# board2.net
KiCad netlist of a schematic drawn in EAGLE
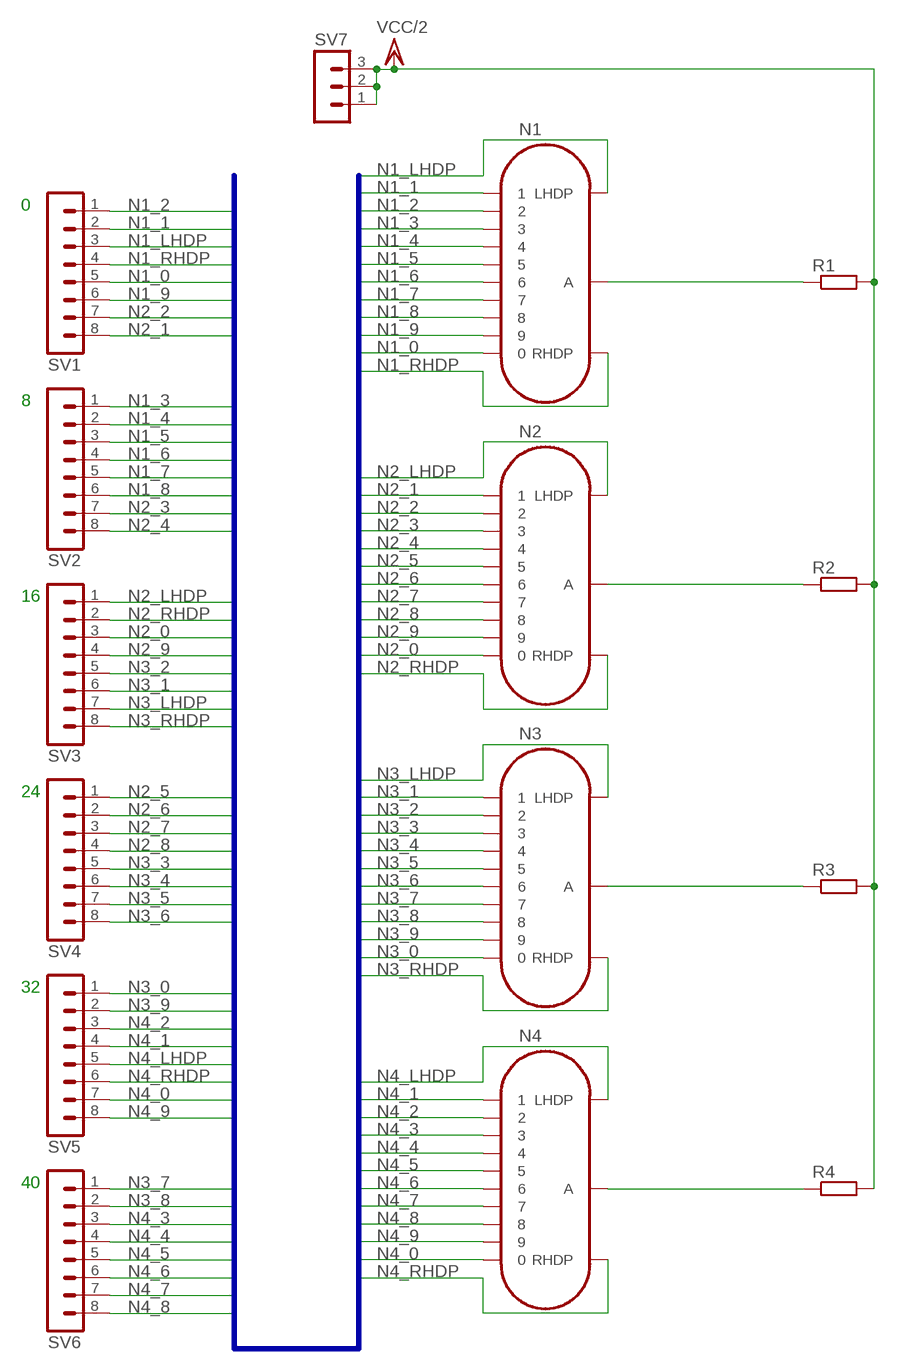
[diagram p0: schematic, sheet 1]

(export (version "E")
  (design (tool "Eeschema 10.0.6"))
  (components
    (comp (ref "N1")
      (value "IN-14")
      (footprint "eagle-import:IN-14")
      (libsource (lib "eagle-import") (part "IN-14"))
    )
    (comp (ref "N2")
      (value "IN-14")
      (footprint "eagle-import:IN-14")
      (libsource (lib "eagle-import") (part "IN-14"))
    )
    (comp (ref "N3")
      (value "IN-14")
      (footprint "eagle-import:IN-14")
      (libsource (lib "eagle-import") (part "IN-14"))
    )
    (comp (ref "N4")
      (value "IN-14")
      (footprint "eagle-import:IN-14")
      (libsource (lib "eagle-import") (part "IN-14"))
    )
    (comp (ref "R1")
      (value "R-EU_0207/7")
      (footprint "eagle-import:0207_7")
      (libsource (lib "eagle-import") (part "R-EU_0207/7"))
    )
    (comp (ref "R2")
      (value "R-EU_0207/7")
      (footprint "eagle-import:0207_7")
      (libsource (lib "eagle-import") (part "R-EU_0207/7"))
    )
    (comp (ref "R3")
      (value "R-EU_0207/7")
      (footprint "eagle-import:0207_7")
      (libsource (lib "eagle-import") (part "R-EU_0207/7"))
    )
    (comp (ref "R4")
      (value "R-EU_0207/7")
      (footprint "eagle-import:0207_7")
      (libsource (lib "eagle-import") (part "R-EU_0207/7"))
    )
    (comp (ref "SV1")
      (value "MA08-1")
      (footprint "eagle-import:MA08-1")
      (libsource (lib "eagle-import") (part "MA08-1"))
    )
    (comp (ref "SV2")
      (value "MA08-1")
      (footprint "eagle-import:MA08-1")
      (libsource (lib "eagle-import") (part "MA08-1"))
    )
    (comp (ref "SV3")
      (value "MA08-1")
      (footprint "eagle-import:MA08-1")
      (libsource (lib "eagle-import") (part "MA08-1"))
    )
    (comp (ref "SV4")
      (value "MA08-1")
      (footprint "eagle-import:MA08-1")
      (libsource (lib "eagle-import") (part "MA08-1"))
    )
    (comp (ref "SV5")
      (value "MA08-1")
      (footprint "eagle-import:MA08-1")
      (libsource (lib "eagle-import") (part "MA08-1"))
    )
    (comp (ref "SV6")
      (value "MA08-1")
      (footprint "eagle-import:MA08-1")
      (libsource (lib "eagle-import") (part "MA08-1"))
    )
    (comp (ref "SV7")
      (value "MA03-1")
      (footprint "eagle-import:MA03-1")
      (libsource (lib "eagle-import") (part "MA03-1"))
    )
  )
  (nets
    (net (code "1") (name "/N1_0") (class "Default")
      (node (ref "N1") (pin "0") (pinfunction "0_0") (pintype "bidirectional"))
      (node (ref "SV1") (pin "5") (pinfunction "5_5") (pintype "passive"))
    )
    (net (code "2") (name "/N1_1") (class "Default")
      (node (ref "N1") (pin "1") (pinfunction "1_1") (pintype "bidirectional"))
      (node (ref "SV1") (pin "2") (pinfunction "2_2") (pintype "passive"))
    )
    (net (code "3") (name "/N1_2") (class "Default")
      (node (ref "N1") (pin "2") (pinfunction "2_2") (pintype "bidirectional"))
      (node (ref "SV1") (pin "1") (pinfunction "1_1") (pintype "passive"))
    )
    (net (code "4") (name "/N1_3") (class "Default")
      (node (ref "N1") (pin "3") (pinfunction "3_3") (pintype "bidirectional"))
      (node (ref "SV2") (pin "1") (pinfunction "1_1") (pintype "passive"))
    )
    (net (code "5") (name "/N1_4") (class "Default")
      (node (ref "N1") (pin "4") (pinfunction "4_4") (pintype "bidirectional"))
      (node (ref "SV2") (pin "2") (pinfunction "2_2") (pintype "passive"))
    )
    (net (code "6") (name "/N1_5") (class "Default")
      (node (ref "N1") (pin "5") (pinfunction "5_5") (pintype "bidirectional"))
      (node (ref "SV2") (pin "3") (pinfunction "3_3") (pintype "passive"))
    )
    (net (code "7") (name "/N1_6") (class "Default")
      (node (ref "N1") (pin "6") (pinfunction "6_6") (pintype "bidirectional"))
      (node (ref "SV2") (pin "4") (pinfunction "4_4") (pintype "passive"))
    )
    (net (code "8") (name "/N1_7") (class "Default")
      (node (ref "N1") (pin "7") (pinfunction "7_7") (pintype "bidirectional"))
      (node (ref "SV2") (pin "5") (pinfunction "5_5") (pintype "passive"))
    )
    (net (code "9") (name "/N1_8") (class "Default")
      (node (ref "N1") (pin "8") (pinfunction "8_8") (pintype "bidirectional"))
      (node (ref "SV2") (pin "6") (pinfunction "6_6") (pintype "passive"))
    )
    (net (code "10") (name "/N1_9") (class "Default")
      (node (ref "N1") (pin "9") (pinfunction "9_9") (pintype "bidirectional"))
      (node (ref "SV1") (pin "6") (pinfunction "6_6") (pintype "passive"))
    )
    (net (code "11") (name "/N1_LHDP") (class "Default")
      (node (ref "N1") (pin "LHDP") (pinfunction "LHDP_LHDP") (pintype "bidirectional"))
      (node (ref "SV1") (pin "3") (pinfunction "3_3") (pintype "passive"))
    )
    (net (code "12") (name "/N1_RHDP") (class "Default")
      (node (ref "N1") (pin "RHDP") (pinfunction "RHDP_RHDP") (pintype "bidirectional"))
      (node (ref "SV1") (pin "4") (pinfunction "4_4") (pintype "passive"))
    )
    (net (code "13") (name "/N2_0") (class "Default")
      (node (ref "N2") (pin "0") (pinfunction "0_0") (pintype "bidirectional"))
      (node (ref "SV3") (pin "3") (pinfunction "3_3") (pintype "passive"))
    )
    (net (code "14") (name "/N2_1") (class "Default")
      (node (ref "N2") (pin "1") (pinfunction "1_1") (pintype "bidirectional"))
      (node (ref "SV1") (pin "8") (pinfunction "8_8") (pintype "passive"))
    )
    (net (code "15") (name "/N2_2") (class "Default")
      (node (ref "N2") (pin "2") (pinfunction "2_2") (pintype "bidirectional"))
      (node (ref "SV1") (pin "7") (pinfunction "7_7") (pintype "passive"))
    )
    (net (code "16") (name "/N2_3") (class "Default")
      (node (ref "N2") (pin "3") (pinfunction "3_3") (pintype "bidirectional"))
      (node (ref "SV2") (pin "7") (pinfunction "7_7") (pintype "passive"))
    )
    (net (code "17") (name "/N2_4") (class "Default")
      (node (ref "N2") (pin "4") (pinfunction "4_4") (pintype "bidirectional"))
      (node (ref "SV2") (pin "8") (pinfunction "8_8") (pintype "passive"))
    )
    (net (code "18") (name "/N2_5") (class "Default")
      (node (ref "N2") (pin "5") (pinfunction "5_5") (pintype "bidirectional"))
      (node (ref "SV4") (pin "1") (pinfunction "1_1") (pintype "passive"))
    )
    (net (code "19") (name "/N2_6") (class "Default")
      (node (ref "N2") (pin "6") (pinfunction "6_6") (pintype "bidirectional"))
      (node (ref "SV4") (pin "2") (pinfunction "2_2") (pintype "passive"))
    )
    (net (code "20") (name "/N2_7") (class "Default")
      (node (ref "N2") (pin "7") (pinfunction "7_7") (pintype "bidirectional"))
      (node (ref "SV4") (pin "3") (pinfunction "3_3") (pintype "passive"))
    )
    (net (code "21") (name "/N2_8") (class "Default")
      (node (ref "N2") (pin "8") (pinfunction "8_8") (pintype "bidirectional"))
      (node (ref "SV4") (pin "4") (pinfunction "4_4") (pintype "passive"))
    )
    (net (code "22") (name "/N2_9") (class "Default")
      (node (ref "N2") (pin "9") (pinfunction "9_9") (pintype "bidirectional"))
      (node (ref "SV3") (pin "4") (pinfunction "4_4") (pintype "passive"))
    )
    (net (code "23") (name "/N2_LHDP") (class "Default")
      (node (ref "N2") (pin "LHDP") (pinfunction "LHDP_LHDP") (pintype "bidirectional"))
      (node (ref "SV3") (pin "1") (pinfunction "1_1") (pintype "passive"))
    )
    (net (code "24") (name "/N2_RHDP") (class "Default")
      (node (ref "N2") (pin "RHDP") (pinfunction "RHDP_RHDP") (pintype "bidirectional"))
      (node (ref "SV3") (pin "2") (pinfunction "2_2") (pintype "passive"))
    )
    (net (code "25") (name "/N3_0") (class "Default")
      (node (ref "N3") (pin "0") (pinfunction "0_0") (pintype "bidirectional"))
      (node (ref "SV5") (pin "1") (pinfunction "1_1") (pintype "passive"))
    )
    (net (code "26") (name "/N3_1") (class "Default")
      (node (ref "N3") (pin "1") (pinfunction "1_1") (pintype "bidirectional"))
      (node (ref "SV3") (pin "6") (pinfunction "6_6") (pintype "passive"))
    )
    (net (code "27") (name "/N3_2") (class "Default")
      (node (ref "N3") (pin "2") (pinfunction "2_2") (pintype "bidirectional"))
      (node (ref "SV3") (pin "5") (pinfunction "5_5") (pintype "passive"))
    )
    (net (code "28") (name "/N3_3") (class "Default")
      (node (ref "N3") (pin "3") (pinfunction "3_3") (pintype "bidirectional"))
      (node (ref "SV4") (pin "5") (pinfunction "5_5") (pintype "passive"))
    )
    (net (code "29") (name "/N3_4") (class "Default")
      (node (ref "N3") (pin "4") (pinfunction "4_4") (pintype "bidirectional"))
      (node (ref "SV4") (pin "6") (pinfunction "6_6") (pintype "passive"))
    )
    (net (code "30") (name "/N3_5") (class "Default")
      (node (ref "N3") (pin "5") (pinfunction "5_5") (pintype "bidirectional"))
      (node (ref "SV4") (pin "7") (pinfunction "7_7") (pintype "passive"))
    )
    (net (code "31") (name "/N3_6") (class "Default")
      (node (ref "N3") (pin "6") (pinfunction "6_6") (pintype "bidirectional"))
      (node (ref "SV4") (pin "8") (pinfunction "8_8") (pintype "passive"))
    )
    (net (code "32") (name "/N3_7") (class "Default")
      (node (ref "N3") (pin "7") (pinfunction "7_7") (pintype "bidirectional"))
      (node (ref "SV6") (pin "1") (pinfunction "1_1") (pintype "passive"))
    )
    (net (code "33") (name "/N3_8") (class "Default")
      (node (ref "N3") (pin "8") (pinfunction "8_8") (pintype "bidirectional"))
      (node (ref "SV6") (pin "2") (pinfunction "2_2") (pintype "passive"))
    )
    (net (code "34") (name "/N3_9") (class "Default")
      (node (ref "N3") (pin "9") (pinfunction "9_9") (pintype "bidirectional"))
      (node (ref "SV5") (pin "2") (pinfunction "2_2") (pintype "passive"))
    )
    (net (code "35") (name "/N3_LHDP") (class "Default")
      (node (ref "N3") (pin "LHDP") (pinfunction "LHDP_LHDP") (pintype "bidirectional"))
      (node (ref "SV3") (pin "7") (pinfunction "7_7") (pintype "passive"))
    )
    (net (code "36") (name "/N3_RHDP") (class "Default")
      (node (ref "N3") (pin "RHDP") (pinfunction "RHDP_RHDP") (pintype "bidirectional"))
      (node (ref "SV3") (pin "8") (pinfunction "8_8") (pintype "passive"))
    )
    (net (code "37") (name "/N4_0") (class "Default")
      (node (ref "N4") (pin "0") (pinfunction "0_0") (pintype "bidirectional"))
      (node (ref "SV5") (pin "7") (pinfunction "7_7") (pintype "passive"))
    )
    (net (code "38") (name "/N4_1") (class "Default")
      (node (ref "N4") (pin "1") (pinfunction "1_1") (pintype "bidirectional"))
      (node (ref "SV5") (pin "4") (pinfunction "4_4") (pintype "passive"))
    )
    (net (code "39") (name "/N4_2") (class "Default")
      (node (ref "N4") (pin "2") (pinfunction "2_2") (pintype "bidirectional"))
      (node (ref "SV5") (pin "3") (pinfunction "3_3") (pintype "passive"))
    )
    (net (code "40") (name "/N4_3") (class "Default")
      (node (ref "N4") (pin "3") (pinfunction "3_3") (pintype "bidirectional"))
      (node (ref "SV6") (pin "3") (pinfunction "3_3") (pintype "passive"))
    )
    (net (code "41") (name "/N4_4") (class "Default")
      (node (ref "N4") (pin "4") (pinfunction "4_4") (pintype "bidirectional"))
      (node (ref "SV6") (pin "4") (pinfunction "4_4") (pintype "passive"))
    )
    (net (code "42") (name "/N4_5") (class "Default")
      (node (ref "N4") (pin "5") (pinfunction "5_5") (pintype "bidirectional"))
      (node (ref "SV6") (pin "5") (pinfunction "5_5") (pintype "passive"))
    )
    (net (code "43") (name "/N4_6") (class "Default")
      (node (ref "N4") (pin "6") (pinfunction "6_6") (pintype "bidirectional"))
      (node (ref "SV6") (pin "6") (pinfunction "6_6") (pintype "passive"))
    )
    (net (code "44") (name "/N4_7") (class "Default")
      (node (ref "N4") (pin "7") (pinfunction "7_7") (pintype "bidirectional"))
      (node (ref "SV6") (pin "7") (pinfunction "7_7") (pintype "passive"))
    )
    (net (code "45") (name "/N4_8") (class "Default")
      (node (ref "N4") (pin "8") (pinfunction "8_8") (pintype "bidirectional"))
      (node (ref "SV6") (pin "8") (pinfunction "8_8") (pintype "passive"))
    )
    (net (code "46") (name "/N4_9") (class "Default")
      (node (ref "N4") (pin "9") (pinfunction "9_9") (pintype "bidirectional"))
      (node (ref "SV5") (pin "8") (pinfunction "8_8") (pintype "passive"))
    )
    (net (code "47") (name "/N4_LHDP") (class "Default")
      (node (ref "N4") (pin "LHDP") (pinfunction "LHDP_LHDP") (pintype "bidirectional"))
      (node (ref "SV5") (pin "5") (pinfunction "5_5") (pintype "passive"))
    )
    (net (code "48") (name "/N4_RHDP") (class "Default")
      (node (ref "N4") (pin "RHDP") (pinfunction "RHDP_RHDP") (pintype "bidirectional"))
      (node (ref "SV5") (pin "6") (pinfunction "6_6") (pintype "passive"))
    )
    (net (code "49") (name "Net-(N1-PadA)") (class "Default")
      (node (ref "N1") (pin "A") (pinfunction "A_A") (pintype "bidirectional"))
      (node (ref "R1") (pin "1") (pinfunction "1_1") (pintype "passive"))
    )
    (net (code "50") (name "Net-(N2-PadA)") (class "Default")
      (node (ref "N2") (pin "A") (pinfunction "A_A") (pintype "bidirectional"))
      (node (ref "R2") (pin "1") (pinfunction "1_1") (pintype "passive"))
    )
    (net (code "51") (name "Net-(N3-PadA)") (class "Default")
      (node (ref "N3") (pin "A") (pinfunction "A_A") (pintype "bidirectional"))
      (node (ref "R3") (pin "1") (pinfunction "1_1") (pintype "passive"))
    )
    (net (code "52") (name "Net-(N4-PadA)") (class "Default")
      (node (ref "N4") (pin "A") (pinfunction "A_A") (pintype "bidirectional"))
      (node (ref "R4") (pin "1") (pinfunction "1_1") (pintype "passive"))
    )
    (net (code "53") (name "VCC{slash}2") (class "Default")
      (node (ref "R1") (pin "2") (pinfunction "2_2") (pintype "passive"))
      (node (ref "R2") (pin "2") (pinfunction "2_2") (pintype "passive"))
      (node (ref "R3") (pin "2") (pinfunction "2_2") (pintype "passive"))
      (node (ref "R4") (pin "2") (pinfunction "2_2") (pintype "passive"))
      (node (ref "SV7") (pin "1") (pinfunction "1_1") (pintype "passive"))
      (node (ref "SV7") (pin "2") (pinfunction "2_2") (pintype "passive"))
      (node (ref "SV7") (pin "3") (pinfunction "3_3") (pintype "passive"))
    )
  )
)
